# Shutdown_2019_v1_1_0.net
KiCad netlist of a schematic drawn in Altium Designer
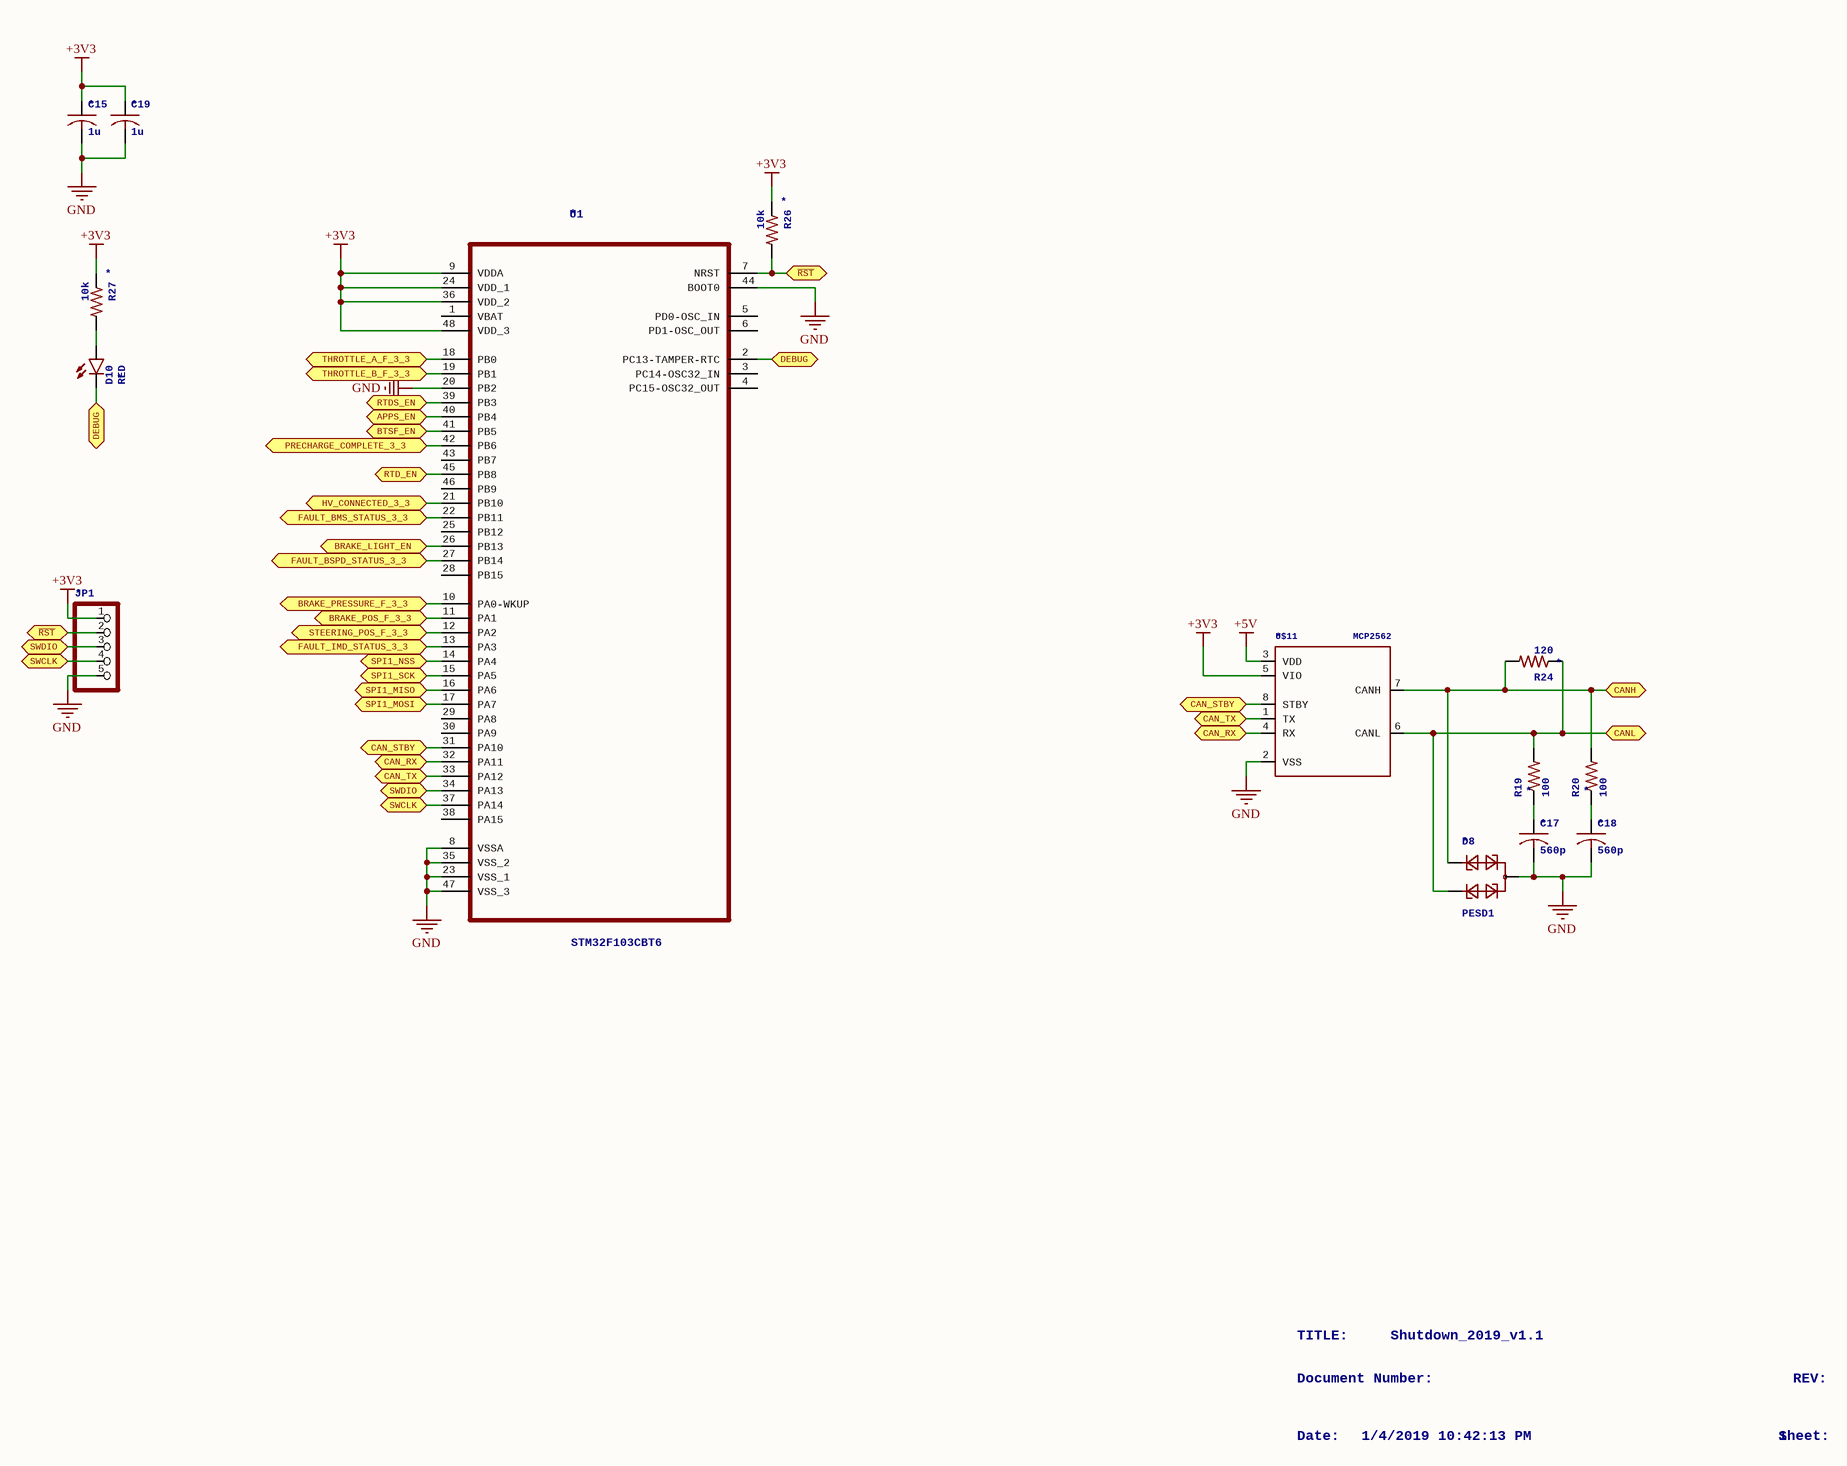
[diagram p0: Shutdown_2019_v1.1_0.SchDoc]

(export (version "E")
  (design (tool "Eeschema 10.0.6"))
  (components
    (comp (ref "C15")
      (value "1u")
      (footprint "C0805")
      (description "CAPACITOR, American symbol")
      (fields (field (name "NAME") "*"))
      (libsource (lib "rcl") (part "C-USC0805"))
    )
    (comp (ref "C17")
      (value "560p")
      (footprint "C0603")
      (description "CAPACITOR, American symbol")
      (fields (field (name "NAME") "*"))
      (libsource (lib "rcl") (part "C-USC0603"))
    )
    (comp (ref "C18")
      (value "560p")
      (footprint "C0603")
      (description "CAPACITOR, American symbol")
      (fields (field (name "NAME") "*"))
      (libsource (lib "rcl") (part "C-USC0603"))
    )
    (comp (ref "C19")
      (value "1u")
      (footprint "C0805")
      (description "CAPACITOR, American symbol")
      (fields (field (name "NAME") "*"))
      (libsource (lib "rcl") (part "C-USC0805"))
    )
    (comp (ref "D8")
      (value "PESD1")
      (footprint "SOT23")
      (description "CAN bus ESD protection diodeSource: http://www.nxp.com/documents/data_sheet/PESD1CAN.pdf")
      (fields (field (name "NAME") "*"))
      (libsource (lib "diode") (part "PESD1CAN"))
    )
    (comp (ref "D10")
      (value "RED")
      (footprint "LED-0603")
      (fields (field (name "NAME") "*"))
      (libsource (lib "SparkFun-LED") (part "LED-RED0603"))
    )
    (comp (ref "JP1")
      (value "PINHD-1X5")
      (footprint "1X05")
      (description "PIN HEADER")
      (fields (field (name "NAME") "*") (field (name "LIBRARYNAME") "Headers_IFE"))
      (libsource (lib "Headers_IFE") (part "PINHD-1X5"))
    )
    (comp (ref "R19")
      (value "100")
      (footprint "R0603")
      (description "RESISTOR, American symbol")
      (fields (field (name "NAME") "*"))
      (libsource (lib "rcl") (part "R-US_R0603"))
    )
    (comp (ref "R20")
      (value "100")
      (footprint "R0603")
      (description "RESISTOR, American symbol")
      (fields (field (name "NAME") "*"))
      (libsource (lib "rcl") (part "R-US_R0603"))
    )
    (comp (ref "R24")
      (value "120")
      (footprint "R0603")
      (description "RESISTOR, American symbol")
      (fields (field (name "NAME") "*"))
      (libsource (lib "rcl") (part "R-US_R0603"))
    )
    (comp (ref "R26")
      (value "10k")
      (footprint "R0603")
      (description "RESISTOR, American symbol")
      (fields (field (name "NAME") "*"))
      (libsource (lib "rcl") (part "R-US_R0603"))
    )
    (comp (ref "R27")
      (value "10k")
      (footprint "R0603")
      (description "RESISTOR, American symbol")
      (fields (field (name "NAME") "*"))
      (libsource (lib "rcl") (part "R-US_R0603"))
    )
    (comp (ref "U$11")
      (value "MCP2562")
      (footprint "SOIC8")
      (fields (field (name "NAME") "*"))
      (libsource (lib "MICROCHIP") (part "MCP2562"))
    )
    (comp (ref "U1")
      (value "STM32F103CBT6")
      (footprint "QFP50P900X900X160-48N")
      (description "Medium-density performance line ARM-based 32-bit MCU")
      (fields
        (field (name "NAME") "*")
        (field (name "LIBRARYNAME") "ST Microelctronics_By_element14_Batch_1")
      )
      (libsource (lib "ST Microelctronics_By_element14_Batch_1") (part "STM32F103CBT6"))
    )
  )
  (nets
    (net (code "1") (name "+3V3") (class "Default")
      (node (ref "C15") (pin "1") (pinfunction "1_1") (pintype "passive"))
      (node (ref "C19") (pin "1") (pinfunction "1_1") (pintype "passive"))
      (node (ref "JP1") (pin "1") (pinfunction "1_1") (pintype "passive"))
      (node (ref "R26") (pin "1") (pinfunction "1_1") (pintype "passive"))
      (node (ref "R27") (pin "1") (pinfunction "1_1") (pintype "passive"))
      (node (ref "U$11") (pin "5") (pinfunction "VIO_5") (pintype "passive"))
      (node (ref "U1") (pin "24") (pinfunction "VDD_1_24") (pintype "passive"))
      (node (ref "U1") (pin "36") (pinfunction "VDD_2_36") (pintype "power_in"))
      (node (ref "U1") (pin "48") (pinfunction "VDD_3_48") (pintype "power_in"))
      (node (ref "U1") (pin "9") (pinfunction "VDDA_9") (pintype "power_in"))
    )
    (net (code "2") (name "+5V") (class "Default")
      (node (ref "U$11") (pin "3") (pinfunction "VDD_3") (pintype "passive"))
    )
    (net (code "3") (name "/APPS_EN") (class "Default")
      (node (ref "U1") (pin "40") (pinfunction "PB4_40") (pintype "passive"))
    )
    (net (code "4") (name "/BRAKE_LIGHT_EN") (class "Default")
      (node (ref "U1") (pin "26") (pinfunction "PB13_26") (pintype "passive"))
    )
    (net (code "5") (name "/BRAKE_POS_F_3_3") (class "Default")
      (node (ref "U1") (pin "11") (pinfunction "PA1_11") (pintype "passive"))
    )
    (net (code "6") (name "/BRAKE_PRESSURE_F_3_3") (class "Default")
      (node (ref "U1") (pin "10") (pinfunction "PA0-WKUP_10") (pintype "passive"))
    )
    (net (code "7") (name "/BTSF_EN") (class "Default")
      (node (ref "U1") (pin "41") (pinfunction "PB5_41") (pintype "passive"))
    )
    (net (code "8") (name "/CANH") (class "Default")
      (node (ref "D8") (pin "1") (pinfunction "1_1") (pintype "passive"))
      (node (ref "R20") (pin "2") (pinfunction "2_2") (pintype "passive"))
      (node (ref "R24") (pin "2") (pinfunction "2_2") (pintype "passive"))
      (node (ref "U$11") (pin "7") (pinfunction "CANH_7") (pintype "passive"))
    )
    (net (code "9") (name "/CANL") (class "Default")
      (node (ref "D8") (pin "2") (pinfunction "2_2") (pintype "passive"))
      (node (ref "R19") (pin "2") (pinfunction "2_2") (pintype "passive"))
      (node (ref "R24") (pin "1") (pinfunction "1_1") (pintype "passive"))
      (node (ref "U$11") (pin "6") (pinfunction "CANL_6") (pintype "passive"))
    )
    (net (code "10") (name "/CAN_RX") (class "Default")
      (node (ref "U$11") (pin "4") (pinfunction "RX_4") (pintype "passive"))
      (node (ref "U1") (pin "32") (pinfunction "PA11_32") (pintype "power_in"))
    )
    (net (code "11") (name "/CAN_STBY") (class "Default")
      (node (ref "U$11") (pin "8") (pinfunction "STBY_8") (pintype "passive"))
      (node (ref "U1") (pin "31") (pinfunction "PA10_31") (pintype "passive"))
    )
    (net (code "12") (name "/CAN_TX") (class "Default")
      (node (ref "U$11") (pin "1") (pinfunction "TX_1") (pintype "passive"))
      (node (ref "U1") (pin "33") (pinfunction "PA12_33") (pintype "passive"))
    )
    (net (code "13") (name "/DEBUG") (class "Default")
      (node (ref "D10") (pin "C") (pinfunction "C_C") (pintype "passive"))
      (node (ref "U1") (pin "2") (pinfunction "PC13-TAMPER-RTC_2") (pintype "passive"))
    )
    (net (code "14") (name "/FAULT_BMS_STATUS_3_3") (class "Default")
      (node (ref "U1") (pin "22") (pinfunction "PB11_22") (pintype "passive"))
    )
    (net (code "15") (name "/FAULT_BSPD_STATUS_3_3") (class "Default")
      (node (ref "U1") (pin "27") (pinfunction "PB14_27") (pintype "passive"))
    )
    (net (code "16") (name "/FAULT_IMD_STATUS_3_3") (class "Default")
      (node (ref "U1") (pin "13") (pinfunction "PA3_13") (pintype "passive"))
    )
    (net (code "17") (name "/HV_CONNECTED_3_3") (class "Default")
      (node (ref "U1") (pin "21") (pinfunction "PB10_21") (pintype "passive"))
    )
    (net (code "18") (name "/PRECHARGE_COMPLETE_3_3") (class "Default")
      (node (ref "U1") (pin "42") (pinfunction "PB6_42") (pintype "passive"))
    )
    (net (code "19") (name "/RTDS_EN") (class "Default")
      (node (ref "U1") (pin "39") (pinfunction "PB3_39") (pintype "passive"))
    )
    (net (code "20") (name "/RTD_EN") (class "Default")
      (node (ref "U1") (pin "45") (pinfunction "PB8_45") (pintype "passive"))
    )
    (net (code "21") (name "/SPI1_MISO") (class "Default")
      (node (ref "U1") (pin "16") (pinfunction "PA6_16") (pintype "passive"))
    )
    (net (code "22") (name "/SPI1_MOSI") (class "Default")
      (node (ref "U1") (pin "17") (pinfunction "PA7_17") (pintype "passive"))
    )
    (net (code "23") (name "/SPI1_NSS") (class "Default")
      (node (ref "U1") (pin "14") (pinfunction "PA4_14") (pintype "passive"))
    )
    (net (code "24") (name "/SPI1_SCK") (class "Default")
      (node (ref "U1") (pin "15") (pinfunction "PA5_15") (pintype "passive"))
    )
    (net (code "25") (name "/STEERING_POS_F_3_3") (class "Default")
      (node (ref "U1") (pin "12") (pinfunction "PA2_12") (pintype "passive"))
    )
    (net (code "26") (name "/SWCLK") (class "Default")
      (node (ref "JP1") (pin "4") (pinfunction "4_4") (pintype "passive"))
      (node (ref "U1") (pin "37") (pinfunction "PA14_37") (pintype "passive"))
    )
    (net (code "27") (name "/SWDIO") (class "Default")
      (node (ref "JP1") (pin "3") (pinfunction "3_3") (pintype "passive"))
      (node (ref "U1") (pin "34") (pinfunction "PA13_34") (pintype "passive"))
    )
    (net (code "28") (name "/THROTTLE_A_F_3_3") (class "Default")
      (node (ref "U1") (pin "18") (pinfunction "PB0_18") (pintype "passive"))
    )
    (net (code "29") (name "/THROTTLE_B_F_3_3") (class "Default")
      (node (ref "U1") (pin "19") (pinfunction "PB1_19") (pintype "passive"))
    )
    (net (code "30") (name "/~{RST}") (class "Default")
      (node (ref "JP1") (pin "2") (pinfunction "2_2") (pintype "passive"))
      (node (ref "R26") (pin "2") (pinfunction "2_2") (pintype "passive"))
      (node (ref "U1") (pin "7") (pinfunction "NRST_7") (pintype "passive"))
    )
    (net (code "31") (name "GND") (class "Default")
      (node (ref "C15") (pin "2") (pinfunction "2_2") (pintype "passive"))
      (node (ref "C17") (pin "2") (pinfunction "2_2") (pintype "passive"))
      (node (ref "C18") (pin "2") (pinfunction "2_2") (pintype "passive"))
      (node (ref "C19") (pin "2") (pinfunction "2_2") (pintype "passive"))
      (node (ref "D8") (pin "3") (pinfunction "3_3") (pintype "passive"))
      (node (ref "JP1") (pin "5") (pinfunction "5_5") (pintype "passive"))
      (node (ref "U$11") (pin "2") (pinfunction "VSS_2") (pintype "passive"))
      (node (ref "U1") (pin "20") (pinfunction "PB2_20") (pintype "passive"))
      (node (ref "U1") (pin "23") (pinfunction "VSS_1_23") (pintype "passive"))
      (node (ref "U1") (pin "35") (pinfunction "VSS_2_35") (pintype "passive"))
      (node (ref "U1") (pin "44") (pinfunction "BOOT0_44") (pintype "passive"))
      (node (ref "U1") (pin "47") (pinfunction "VSS_3_47") (pintype "passive"))
      (node (ref "U1") (pin "8") (pinfunction "VSSA_8") (pintype "passive"))
    )
    (net (code "32") (name "Net-(C17-Pad1)") (class "Default")
      (node (ref "C17") (pin "1") (pinfunction "1_1") (pintype "passive"))
      (node (ref "R19") (pin "1") (pinfunction "1_1") (pintype "passive"))
    )
    (net (code "33") (name "Net-(C18-Pad1)") (class "Default")
      (node (ref "C18") (pin "1") (pinfunction "1_1") (pintype "passive"))
      (node (ref "R20") (pin "1") (pinfunction "1_1") (pintype "passive"))
    )
    (net (code "34") (name "Net-(D10-PadA)") (class "Default")
      (node (ref "D10") (pin "A") (pinfunction "A_A") (pintype "passive"))
      (node (ref "R27") (pin "2") (pinfunction "2_2") (pintype "passive"))
    )
    (net (code "35") (name "unconnected-(U1-PA8-Pad29)") (class "Default")
      (node (ref "U1") (pin "29") (pinfunction "PA8_29") (pintype "passive"))
    )
    (net (code "36") (name "unconnected-(U1-PA9-Pad30)") (class "Default")
      (node (ref "U1") (pin "30") (pinfunction "PA9_30") (pintype "passive"))
    )
    (net (code "37") (name "unconnected-(U1-PA15-Pad38)") (class "Default")
      (node (ref "U1") (pin "38") (pinfunction "PA15_38") (pintype "passive"))
    )
    (net (code "38") (name "unconnected-(U1-PB7-Pad43)") (class "Default")
      (node (ref "U1") (pin "43") (pinfunction "PB7_43") (pintype "passive"))
    )
    (net (code "39") (name "unconnected-(U1-PB9-Pad46)") (class "Default")
      (node (ref "U1") (pin "46") (pinfunction "PB9_46") (pintype "passive"))
    )
    (net (code "40") (name "unconnected-(U1-PB12-Pad25)") (class "Default")
      (node (ref "U1") (pin "25") (pinfunction "PB12_25") (pintype "passive"))
    )
    (net (code "41") (name "unconnected-(U1-PB15-Pad28)") (class "Default")
      (node (ref "U1") (pin "28") (pinfunction "PB15_28") (pintype "passive"))
    )
    (net (code "42") (name "unconnected-(U1-PC14-OSC32_IN-Pad3)") (class "Default")
      (node (ref "U1") (pin "3") (pinfunction "PC14-OSC32_IN_3") (pintype "passive"))
    )
    (net (code "43") (name "unconnected-(U1-PC15-OSC32_OUT-Pad4)") (class "Default")
      (node (ref "U1") (pin "4") (pinfunction "PC15-OSC32_OUT_4") (pintype "passive"))
    )
    (net (code "44") (name "unconnected-(U1-PD0-OSC_IN-Pad5)") (class "Default")
      (node (ref "U1") (pin "5") (pinfunction "PD0-OSC_IN_5") (pintype "passive"))
    )
    (net (code "45") (name "unconnected-(U1-PD1-OSC_OUT-Pad6)") (class "Default")
      (node (ref "U1") (pin "6") (pinfunction "PD1-OSC_OUT_6") (pintype "passive"))
    )
    (net (code "46") (name "unconnected-(U1-VBAT-Pad1)") (class "Default")
      (node (ref "U1") (pin "1") (pinfunction "VBAT_1") (pintype "passive"))
    )
  )
)
